# SpectroSlave.net
KiCad netlist of a schematic drawn in EAGLE
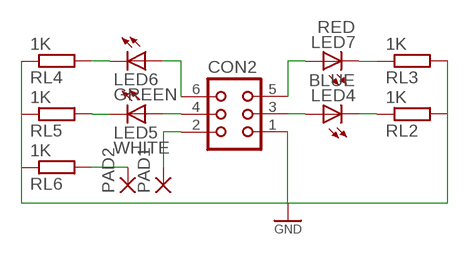
[diagram p0: schematic, sheet 1]

(export (version "E")
  (design (tool "Eeschema 10.0.6"))
  (components
    (comp (ref "CON2")
      (value "CON06L")
      (footprint "eagle-import:CON06L")
      (libsource (lib "eagle-import") (part "CON06L"))
    )
    (comp (ref "LED4")
      (value "BLUE")
      (footprint "eagle-import:LED3MM")
      (libsource (lib "eagle-import") (part "LED3MM"))
    )
    (comp (ref "LED5")
      (value "WHITE")
      (footprint "eagle-import:LED3MM")
      (libsource (lib "eagle-import") (part "LED3MM"))
    )
    (comp (ref "LED6")
      (value "GREEN")
      (footprint "eagle-import:LED3MM")
      (libsource (lib "eagle-import") (part "LED3MM"))
    )
    (comp (ref "LED7")
      (value "RED")
      (footprint "eagle-import:LED3MM")
      (libsource (lib "eagle-import") (part "LED3MM"))
    )
    (comp (ref "PAD1")
      (value "SMD5")
      (footprint "eagle-import:SMD2,54-5,08")
      (libsource (lib "eagle-import") (part "SMD5"))
    )
    (comp (ref "PAD2")
      (value "SMD5")
      (footprint "eagle-import:SMD2,54-5,08")
      (libsource (lib "eagle-import") (part "SMD5"))
    )
    (comp (ref "RL2")
      (value "1K")
      (footprint "eagle-import:R0805")
      (libsource (lib "eagle-import") (part "R-EU_R0805"))
    )
    (comp (ref "RL3")
      (value "1K")
      (footprint "eagle-import:R0805")
      (libsource (lib "eagle-import") (part "R-EU_R0805"))
    )
    (comp (ref "RL4")
      (value "1K")
      (footprint "eagle-import:R0805")
      (libsource (lib "eagle-import") (part "R-EU_R0805"))
    )
    (comp (ref "RL5")
      (value "1K")
      (footprint "eagle-import:R0805")
      (libsource (lib "eagle-import") (part "R-EU_R0805"))
    )
    (comp (ref "RL6")
      (value "1K")
      (footprint "eagle-import:R0805")
      (libsource (lib "eagle-import") (part "R-EU_R0805"))
    )
  )
  (nets
    (net (code "1") (name "GND") (class "Default")
      (node (ref "CON2") (pin "1") (pinfunction "1_1") (pintype "passive"))
      (node (ref "RL2") (pin "2") (pinfunction "2_2") (pintype "passive"))
      (node (ref "RL3") (pin "2") (pinfunction "2_2") (pintype "passive"))
      (node (ref "RL4") (pin "1") (pinfunction "1_1") (pintype "passive"))
      (node (ref "RL5") (pin "1") (pinfunction "1_1") (pintype "passive"))
      (node (ref "RL6") (pin "1") (pinfunction "1_1") (pintype "passive"))
    )
    (net (code "2") (name "Net-(CON2-Pad3)") (class "Default")
      (node (ref "CON2") (pin "3") (pinfunction "3_3") (pintype "passive"))
      (node (ref "LED4") (pin "A") (pinfunction "A_A") (pintype "passive"))
    )
    (net (code "3") (name "Net-(CON2-Pad4)") (class "Default")
      (node (ref "CON2") (pin "4") (pinfunction "4_4") (pintype "passive"))
      (node (ref "LED5") (pin "A") (pinfunction "A_A") (pintype "passive"))
    )
    (net (code "4") (name "Net-(CON2-Pad5)") (class "Default")
      (node (ref "CON2") (pin "5") (pinfunction "5_5") (pintype "passive"))
      (node (ref "LED7") (pin "A") (pinfunction "A_A") (pintype "passive"))
    )
    (net (code "5") (name "Net-(CON2-Pad6)") (class "Default")
      (node (ref "CON2") (pin "6") (pinfunction "6_6") (pintype "passive"))
      (node (ref "LED6") (pin "A") (pinfunction "A_A") (pintype "passive"))
    )
    (net (code "6") (name "Net-(LED4-C)") (class "Default")
      (node (ref "LED4") (pin "K") (pinfunction "C_K") (pintype "passive"))
      (node (ref "RL2") (pin "1") (pinfunction "1_1") (pintype "passive"))
    )
    (net (code "7") (name "Net-(LED5-C)") (class "Default")
      (node (ref "LED5") (pin "K") (pinfunction "C_K") (pintype "passive"))
      (node (ref "RL5") (pin "2") (pinfunction "2_2") (pintype "passive"))
    )
    (net (code "8") (name "Net-(LED6-C)") (class "Default")
      (node (ref "LED6") (pin "K") (pinfunction "C_K") (pintype "passive"))
      (node (ref "RL4") (pin "2") (pinfunction "2_2") (pintype "passive"))
    )
    (net (code "9") (name "Net-(LED7-C)") (class "Default")
      (node (ref "LED7") (pin "K") (pinfunction "C_K") (pintype "passive"))
      (node (ref "RL3") (pin "1") (pinfunction "1_1") (pintype "passive"))
    )
    (net (code "10") (name "Net-(PAD1-P)") (class "Default")
      (node (ref "CON2") (pin "2") (pinfunction "2_2") (pintype "passive"))
      (node (ref "PAD1") (pin "1") (pinfunction "P_1") (pintype "passive"))
    )
    (net (code "11") (name "Net-(PAD2-P)") (class "Default")
      (node (ref "PAD2") (pin "1") (pinfunction "P_1") (pintype "passive"))
      (node (ref "RL6") (pin "2") (pinfunction "2_2") (pintype "passive"))
    )
  )
)
